# Sunrise.net
KiCad netlist of a schematic drawn in EAGLE
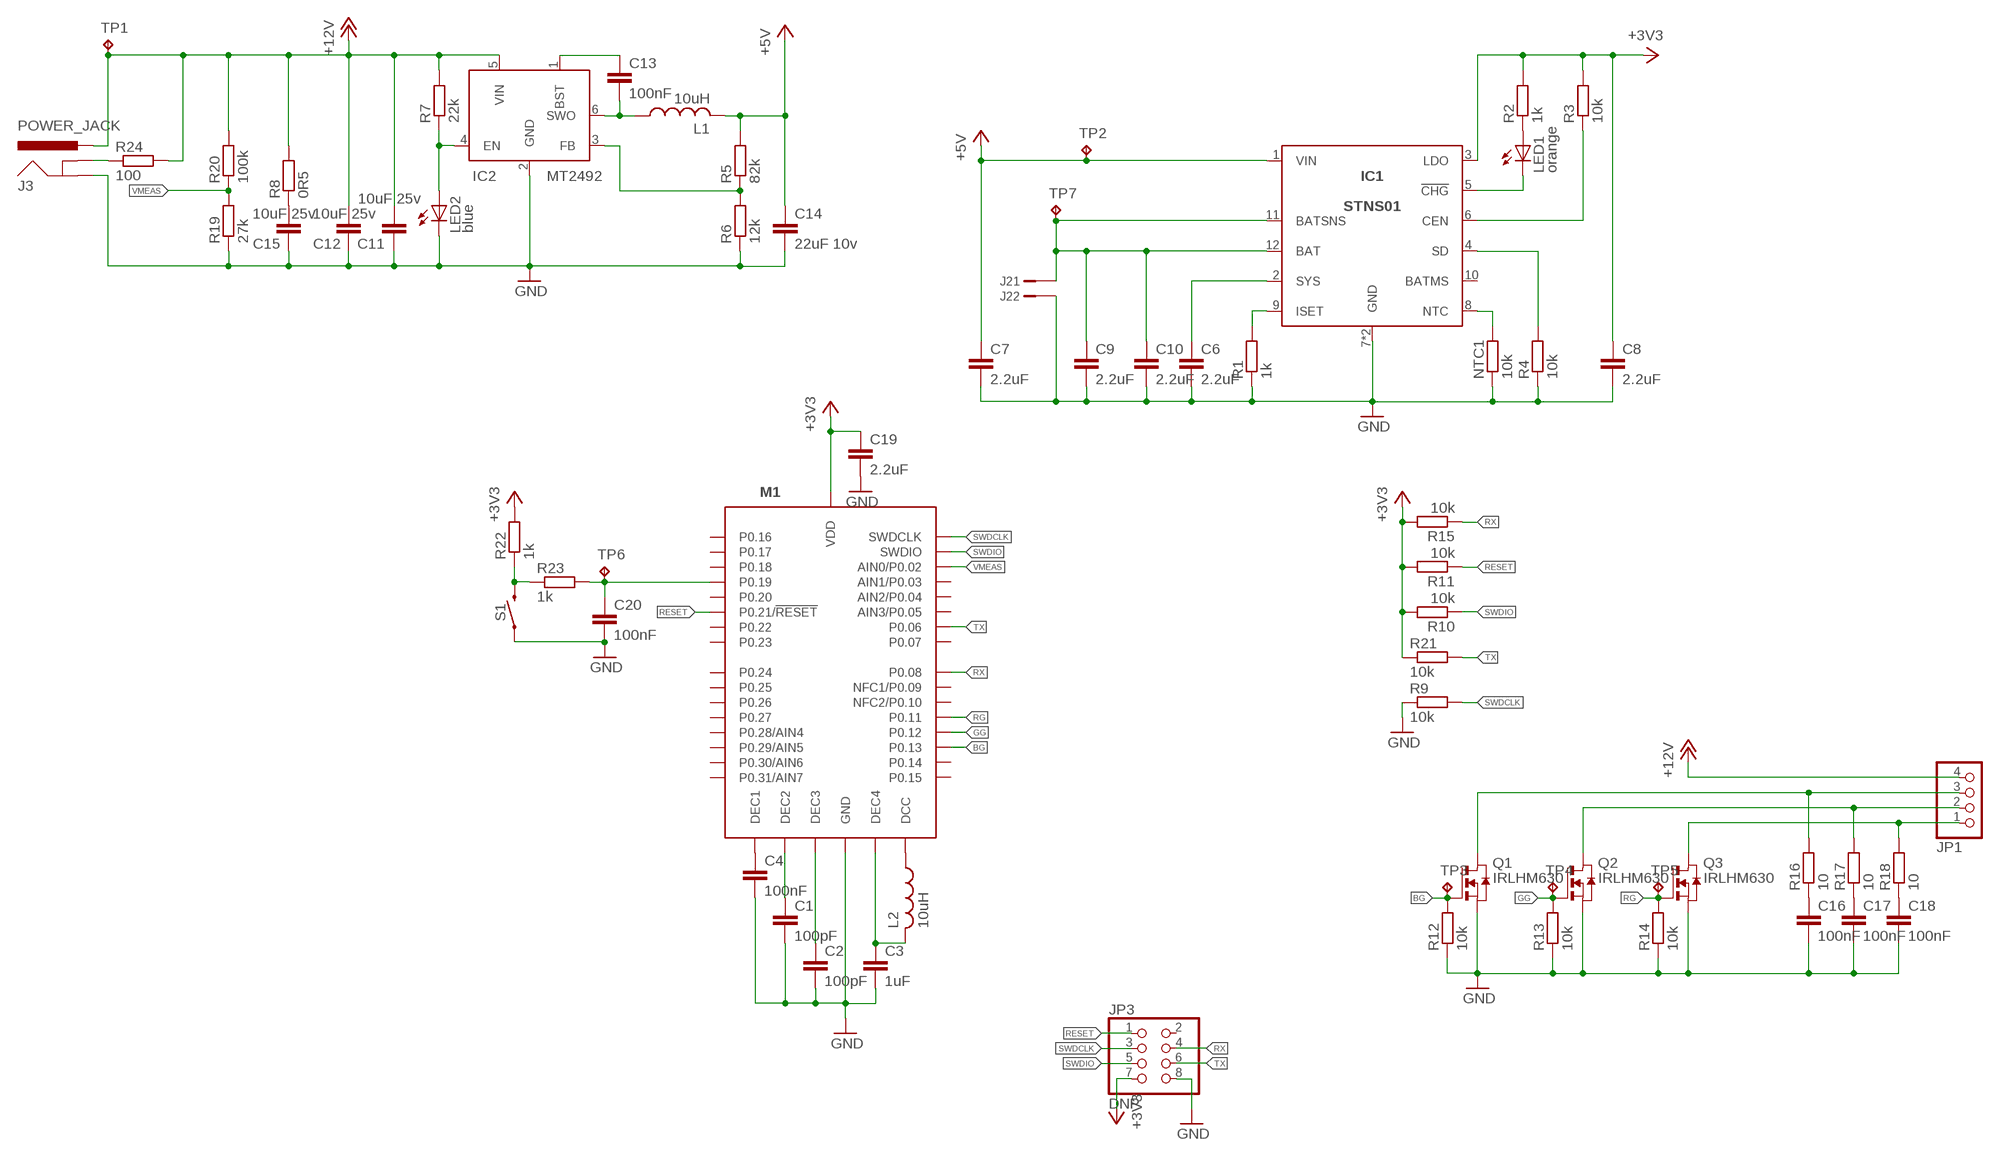
[diagram p0: schematic, sheet 1]

(export (version "E")
  (design (tool "Eeschema 10.0.6"))
  (components
    (comp (ref "C1")
      (value "100pF")
      (footprint "eagle-import:C0402K")
      (libsource (lib "eagle-import") (part "C-EUC0402K"))
    )
    (comp (ref "C2")
      (value "100pF")
      (footprint "eagle-import:C0402K")
      (libsource (lib "eagle-import") (part "C-EUC0402K"))
    )
    (comp (ref "C3")
      (value "1uF")
      (footprint "eagle-import:C0603K")
      (libsource (lib "eagle-import") (part "C-EUC0603K"))
    )
    (comp (ref "C4")
      (value "100nF")
      (footprint "eagle-import:C0402K")
      (libsource (lib "eagle-import") (part "C-EUC0402K"))
    )
    (comp (ref "C6")
      (value "2.2uF")
      (footprint "eagle-import:C0603K")
      (libsource (lib "eagle-import") (part "C-EUC0603K"))
    )
    (comp (ref "C7")
      (value "2.2uF")
      (footprint "eagle-import:C0603K")
      (libsource (lib "eagle-import") (part "C-EUC0603K"))
    )
    (comp (ref "C8")
      (value "2.2uF")
      (footprint "eagle-import:C0603K")
      (libsource (lib "eagle-import") (part "C-EUC0603K"))
    )
    (comp (ref "C9")
      (value "2.2uF")
      (footprint "eagle-import:C0603K")
      (libsource (lib "eagle-import") (part "C-EUC0603K"))
    )
    (comp (ref "C10")
      (value "2.2uF")
      (footprint "eagle-import:C0603K")
      (libsource (lib "eagle-import") (part "C-EUC0603K"))
    )
    (comp (ref "C11")
      (value "10uF 25v")
      (footprint "eagle-import:C1206K")
      (libsource (lib "eagle-import") (part "C-EUC1206K"))
    )
    (comp (ref "C12")
      (value "10uF 25v")
      (footprint "eagle-import:C1206K")
      (libsource (lib "eagle-import") (part "C-EUC1206K"))
    )
    (comp (ref "C13")
      (value "100nF")
      (footprint "eagle-import:C0402K")
      (libsource (lib "eagle-import") (part "C-EUC0402K"))
    )
    (comp (ref "C14")
      (value "22uF 10v")
      (footprint "eagle-import:C1206K")
      (libsource (lib "eagle-import") (part "C-EUC1206K"))
    )
    (comp (ref "C15")
      (value "10uF 25v")
      (footprint "eagle-import:C1206K")
      (libsource (lib "eagle-import") (part "C-EUC1206K"))
    )
    (comp (ref "C16")
      (value "100nF")
      (footprint "eagle-import:C0402K")
      (libsource (lib "eagle-import") (part "C-EUC0402K"))
    )
    (comp (ref "C17")
      (value "100nF")
      (footprint "eagle-import:C0402K")
      (libsource (lib "eagle-import") (part "C-EUC0402K"))
    )
    (comp (ref "C18")
      (value "100nF")
      (footprint "eagle-import:C0402K")
      (libsource (lib "eagle-import") (part "C-EUC0402K"))
    )
    (comp (ref "C19")
      (value "2.2uF")
      (footprint "eagle-import:C0603K")
      (libsource (lib "eagle-import") (part "C-EUC0603K"))
    )
    (comp (ref "C20")
      (value "100nF")
      (footprint "eagle-import:C0402K")
      (libsource (lib "eagle-import") (part "C-EUC0402K"))
    )
    (comp (ref "IC1")
      (value "STNS01")
      (footprint "eagle-import:DFN12L-3MM")
      (libsource (lib "eagle-import") (part "STNS01"))
    )
    (comp (ref "IC2")
      (value "MT2492")
      (footprint "eagle-import:SOT23-6")
      (libsource (lib "eagle-import") (part "MT2492"))
    )
    (comp (ref "J2")
      (value "B2B-PH-K-S")
      (footprint "eagle-import:B2B-PH-K-S")
      (libsource (lib "eagle-import") (part "B2B-PH-K-S"))
    )
    (comp (ref "J3")
      (value "POWER_JACK")
      (footprint "eagle-import:POWER_JACK_PTH")
      (libsource (lib "eagle-import") (part "POWER_JACK"))
    )
    (comp (ref "JP1")
      (value "PINHD-1X4/90")
      (footprint "eagle-import:1X04_90")
      (libsource (lib "eagle-import") (part "PINHD-1X4/90"))
    )
    (comp (ref "JP3")
      (value "DNP")
      (footprint "eagle-import:2X04")
      (libsource (lib "eagle-import") (part "PINHD-2X4"))
    )
    (comp (ref "L1")
      (value "10uH")
      (footprint "eagle-import:2020-5050")
      (libsource (lib "eagle-import") (part "INDUCTOR5050"))
    )
    (comp (ref "L2")
      (value "10uH")
      (footprint "eagle-import:0603-1608")
      (libsource (lib "eagle-import") (part "INDUCTOR1608"))
    )
    (comp (ref "LED1")
      (value "orange")
      (footprint "eagle-import:CHIP-LED0603")
      (libsource (lib "eagle-import") (part "LEDCHIP-LED0603"))
    )
    (comp (ref "LED2")
      (value "blue")
      (footprint "eagle-import:CHIP-LED0603")
      (libsource (lib "eagle-import") (part "LEDCHIP-LED0603"))
    )
    (comp (ref "M1")
      (value "E73-2G4M04S")
      (footprint "eagle-import:E73-2GM404S")
      (libsource (lib "eagle-import") (part "E73-2G4M04S"))
    )
    (comp (ref "NTC1")
      (value "10k")
      (footprint "eagle-import:R0402")
      (libsource (lib "eagle-import") (part "R-EU_R0402"))
    )
    (comp (ref "Q1")
      (value "IRLHM630")
      (footprint "eagle-import:MLP8-33")
      (libsource (lib "eagle-import") (part "NMOS-MLP8-33"))
    )
    (comp (ref "Q2")
      (value "IRLHM630")
      (footprint "eagle-import:MLP8-33")
      (libsource (lib "eagle-import") (part "NMOS-MLP8-33"))
    )
    (comp (ref "Q3")
      (value "IRLHM630")
      (footprint "eagle-import:MLP8-33")
      (libsource (lib "eagle-import") (part "NMOS-MLP8-33"))
    )
    (comp (ref "R1")
      (value "1k")
      (footprint "eagle-import:R0402")
      (libsource (lib "eagle-import") (part "R-EU_R0402"))
    )
    (comp (ref "R2")
      (value "1k")
      (footprint "eagle-import:R0402")
      (libsource (lib "eagle-import") (part "R-EU_R0402"))
    )
    (comp (ref "R3")
      (value "10k")
      (footprint "eagle-import:R0402")
      (libsource (lib "eagle-import") (part "R-EU_R0402"))
    )
    (comp (ref "R4")
      (value "10k")
      (footprint "eagle-import:R0402")
      (libsource (lib "eagle-import") (part "R-EU_R0402"))
    )
    (comp (ref "R5")
      (value "82k")
      (footprint "eagle-import:R0402")
      (libsource (lib "eagle-import") (part "R-EU_R0402"))
    )
    (comp (ref "R6")
      (value "12k")
      (footprint "eagle-import:R0402")
      (libsource (lib "eagle-import") (part "R-EU_R0402"))
    )
    (comp (ref "R7")
      (value "22k")
      (footprint "eagle-import:R0402")
      (libsource (lib "eagle-import") (part "R-EU_R0402"))
    )
    (comp (ref "R8")
      (value "0R5")
      (footprint "eagle-import:R0402")
      (libsource (lib "eagle-import") (part "R-EU_R0402"))
    )
    (comp (ref "R9")
      (value "10k")
      (footprint "eagle-import:R0402")
      (libsource (lib "eagle-import") (part "R-EU_R0402"))
    )
    (comp (ref "R10")
      (value "10k")
      (footprint "eagle-import:R0402")
      (libsource (lib "eagle-import") (part "R-EU_R0402"))
    )
    (comp (ref "R11")
      (value "10k")
      (footprint "eagle-import:R0402")
      (libsource (lib "eagle-import") (part "R-EU_R0402"))
    )
    (comp (ref "R12")
      (value "10k")
      (footprint "eagle-import:R0402")
      (libsource (lib "eagle-import") (part "R-EU_R0402"))
    )
    (comp (ref "R13")
      (value "10k")
      (footprint "eagle-import:R0402")
      (libsource (lib "eagle-import") (part "R-EU_R0402"))
    )
    (comp (ref "R14")
      (value "10k")
      (footprint "eagle-import:R0402")
      (libsource (lib "eagle-import") (part "R-EU_R0402"))
    )
    (comp (ref "R15")
      (value "10k")
      (footprint "eagle-import:R0402")
      (libsource (lib "eagle-import") (part "R-EU_R0402"))
    )
    (comp (ref "R16")
      (value "10")
      (footprint "eagle-import:R0402")
      (libsource (lib "eagle-import") (part "R-EU_R0402"))
    )
    (comp (ref "R17")
      (value "10")
      (footprint "eagle-import:R0402")
      (libsource (lib "eagle-import") (part "R-EU_R0402"))
    )
    (comp (ref "R18")
      (value "10")
      (footprint "eagle-import:R0402")
      (libsource (lib "eagle-import") (part "R-EU_R0402"))
    )
    (comp (ref "R19")
      (value "27k")
      (footprint "eagle-import:R0402")
      (libsource (lib "eagle-import") (part "R-EU_R0402"))
    )
    (comp (ref "R20")
      (value "100k")
      (footprint "eagle-import:R0402")
      (libsource (lib "eagle-import") (part "R-EU_R0402"))
    )
    (comp (ref "R21")
      (value "10k")
      (footprint "eagle-import:R0402")
      (libsource (lib "eagle-import") (part "R-EU_R0402"))
    )
    (comp (ref "R22")
      (value "1k")
      (footprint "eagle-import:R0402")
      (libsource (lib "eagle-import") (part "R-EU_R0402"))
    )
    (comp (ref "R23")
      (value "1k")
      (footprint "eagle-import:R0402")
      (libsource (lib "eagle-import") (part "R-EU_R0402"))
    )
    (comp (ref "R24")
      (value "100")
      (footprint "eagle-import:R0402")
      (libsource (lib "eagle-import") (part "R-EU_R0402"))
    )
    (comp (ref "S1")
      (value "MOMENTARY-SWITCH-SPST-SMD-5.2MM")
      (footprint "eagle-import:TACTILE_SWITCH_SMD_5.2MM")
      (libsource (lib "eagle-import") (part "MOMENTARY-SWITCH-SPST-SMD-5.2MM"))
    )
    (comp (ref "TP1")
      (value "TPTP10R")
      (footprint "eagle-import:TP10R")
      (libsource (lib "eagle-import") (part "TPTP10R"))
    )
    (comp (ref "TP2")
      (value "TPTP10R")
      (footprint "eagle-import:TP10R")
      (libsource (lib "eagle-import") (part "TPTP10R"))
    )
    (comp (ref "TP3")
      (value "TPTP10R")
      (footprint "eagle-import:TP10R")
      (libsource (lib "eagle-import") (part "TPTP10R"))
    )
    (comp (ref "TP4")
      (value "TPTP10R")
      (footprint "eagle-import:TP10R")
      (libsource (lib "eagle-import") (part "TPTP10R"))
    )
    (comp (ref "TP5")
      (value "TPTP10R")
      (footprint "eagle-import:TP10R")
      (libsource (lib "eagle-import") (part "TPTP10R"))
    )
    (comp (ref "TP6")
      (value "TPTP10R")
      (footprint "eagle-import:TP10R")
      (libsource (lib "eagle-import") (part "TPTP10R"))
    )
    (comp (ref "TP7")
      (value "TPTP10R")
      (footprint "eagle-import:TP10R")
      (libsource (lib "eagle-import") (part "TPTP10R"))
    )
  )
  (nets
    (net (code "1") (name "+3V3") (class "Default")
      (node (ref "C19") (pin "1") (pinfunction "1_1") (pintype "passive"))
      (node (ref "C8") (pin "1") (pinfunction "1_1") (pintype "passive"))
      (node (ref "IC1") (pin "3") (pinfunction "LDO_3") (pintype "power_in"))
      (node (ref "JP3") (pin "7") (pinfunction "7_7") (pintype "passive"))
      (node (ref "M1") (pin "16") (pinfunction "VDD_16") (pintype "power_in"))
      (node (ref "R10") (pin "2") (pinfunction "2_2") (pintype "passive"))
      (node (ref "R11") (pin "2") (pinfunction "2_2") (pintype "passive"))
      (node (ref "R15") (pin "2") (pinfunction "2_2") (pintype "passive"))
      (node (ref "R2") (pin "2") (pinfunction "2_2") (pintype "passive"))
      (node (ref "R21") (pin "1") (pinfunction "1_1") (pintype "passive"))
      (node (ref "R22") (pin "2") (pinfunction "2_2") (pintype "passive"))
      (node (ref "R3") (pin "2") (pinfunction "2_2") (pintype "passive"))
    )
    (net (code "2") (name "+5V") (class "Default")
      (node (ref "C14") (pin "1") (pinfunction "1_1") (pintype "passive"))
      (node (ref "C7") (pin "1") (pinfunction "1_1") (pintype "passive"))
      (node (ref "IC1") (pin "1") (pinfunction "VIN_1") (pintype "power_in"))
      (node (ref "L1") (pin "2") (pinfunction "2_2") (pintype "passive"))
      (node (ref "R5") (pin "2") (pinfunction "2_2") (pintype "passive"))
      (node (ref "TP2") (pin "TP") (pinfunction "TP_TP") (pintype "input"))
    )
    (net (code "3") (name "+12V") (class "Default")
      (node (ref "C11") (pin "1") (pinfunction "1_1") (pintype "passive"))
      (node (ref "C12") (pin "1") (pinfunction "1_1") (pintype "passive"))
      (node (ref "IC2") (pin "5") (pinfunction "VIN_5") (pintype "power_in"))
      (node (ref "J3") (pin "PWR") (pinfunction "PWR_PWR") (pintype "bidirectional"))
      (node (ref "JP1") (pin "4") (pinfunction "4_4") (pintype "passive"))
      (node (ref "R20") (pin "2") (pinfunction "2_2") (pintype "passive"))
      (node (ref "R24") (pin "2") (pinfunction "2_2") (pintype "passive"))
      (node (ref "R7") (pin "2") (pinfunction "2_2") (pintype "passive"))
      (node (ref "R8") (pin "2") (pinfunction "2_2") (pintype "passive"))
      (node (ref "TP1") (pin "TP") (pinfunction "TP_TP") (pintype "input"))
    )
    (net (code "4") (name "BG") (class "Default")
      (node (ref "M1") (pin "28") (pinfunction "P0.13_28") (pintype "bidirectional"))
      (node (ref "Q1") (pin "GATE") (pinfunction "G_GATE") (pintype "passive"))
      (node (ref "R12") (pin "2") (pinfunction "2_2") (pintype "passive"))
      (node (ref "TP3") (pin "TP") (pinfunction "TP_TP") (pintype "input"))
    )
    (net (code "5") (name "GG") (class "Default")
      (node (ref "M1") (pin "27") (pinfunction "P0.12_27") (pintype "bidirectional"))
      (node (ref "Q2") (pin "GATE") (pinfunction "G_GATE") (pintype "passive"))
      (node (ref "R13") (pin "2") (pinfunction "2_2") (pintype "passive"))
      (node (ref "TP4") (pin "TP") (pinfunction "TP_TP") (pintype "input"))
    )
    (net (code "6") (name "GND") (class "Default")
      (node (ref "C1") (pin "2") (pinfunction "2_2") (pintype "passive"))
      (node (ref "C10") (pin "2") (pinfunction "2_2") (pintype "passive"))
      (node (ref "C11") (pin "2") (pinfunction "2_2") (pintype "passive"))
      (node (ref "C12") (pin "2") (pinfunction "2_2") (pintype "passive"))
      (node (ref "C14") (pin "2") (pinfunction "2_2") (pintype "passive"))
      (node (ref "C15") (pin "2") (pinfunction "2_2") (pintype "passive"))
      (node (ref "C16") (pin "2") (pinfunction "2_2") (pintype "passive"))
      (node (ref "C17") (pin "2") (pinfunction "2_2") (pintype "passive"))
      (node (ref "C18") (pin "2") (pinfunction "2_2") (pintype "passive"))
      (node (ref "C19") (pin "2") (pinfunction "2_2") (pintype "passive"))
      (node (ref "C2") (pin "2") (pinfunction "2_2") (pintype "passive"))
      (node (ref "C20") (pin "2") (pinfunction "2_2") (pintype "passive"))
      (node (ref "C3") (pin "2") (pinfunction "2_2") (pintype "passive"))
      (node (ref "C4") (pin "2") (pinfunction "2_2") (pintype "passive"))
      (node (ref "C6") (pin "2") (pinfunction "2_2") (pintype "passive"))
      (node (ref "C7") (pin "2") (pinfunction "2_2") (pintype "passive"))
      (node (ref "C8") (pin "2") (pinfunction "2_2") (pintype "passive"))
      (node (ref "C9") (pin "2") (pinfunction "2_2") (pintype "passive"))
      (node (ref "IC1") (pin "7") (pinfunction "GND_7") (pintype "power_in"))
      (node (ref "IC1") (pin "PAD") (pinfunction "GND_PAD") (pintype "power_in"))
      (node (ref "IC2") (pin "2") (pinfunction "GND_2") (pintype "power_in"))
      (node (ref "J2") (pin "2") (pinfunction "1_2") (pintype "passive"))
      (node (ref "J3") (pin "GND") (pinfunction "GND_GND") (pintype "bidirectional"))
      (node (ref "JP3") (pin "8") (pinfunction "8_8") (pintype "passive"))
      (node (ref "LED2") (pin "C") (pinfunction "C_C") (pintype "passive"))
      (node (ref "M1") (pin "0") (pinfunction "GND_0") (pintype "power_in"))
      (node (ref "M1") (pin "1") (pinfunction "GND_1") (pintype "power_in"))
      (node (ref "M1") (pin "15") (pinfunction "GND_15") (pintype "power_in"))
      (node (ref "M1") (pin "2") (pinfunction "GND_2") (pintype "power_in"))
      (node (ref "M1") (pin "42") (pinfunction "GND_42") (pintype "power_in"))
      (node (ref "M1") (pin "43") (pinfunction "GND_43") (pintype "power_in"))
      (node (ref "NTC1") (pin "1") (pinfunction "1_1") (pintype "passive"))
      (node (ref "Q1") (pin "S1") (pinfunction "S_S1") (pintype "passive"))
      (node (ref "Q1") (pin "S2") (pinfunction "S_S2") (pintype "passive"))
      (node (ref "Q1") (pin "S3") (pinfunction "S_S3") (pintype "passive"))
      (node (ref "Q2") (pin "S1") (pinfunction "S_S1") (pintype "passive"))
      (node (ref "Q2") (pin "S2") (pinfunction "S_S2") (pintype "passive"))
      (node (ref "Q2") (pin "S3") (pinfunction "S_S3") (pintype "passive"))
      (node (ref "Q3") (pin "S1") (pinfunction "S_S1") (pintype "passive"))
      (node (ref "Q3") (pin "S2") (pinfunction "S_S2") (pintype "passive"))
      (node (ref "Q3") (pin "S3") (pinfunction "S_S3") (pintype "passive"))
      (node (ref "R1") (pin "1") (pinfunction "1_1") (pintype "passive"))
      (node (ref "R12") (pin "1") (pinfunction "1_1") (pintype "passive"))
      (node (ref "R13") (pin "1") (pinfunction "1_1") (pintype "passive"))
      (node (ref "R14") (pin "1") (pinfunction "1_1") (pintype "passive"))
      (node (ref "R19") (pin "1") (pinfunction "1_1") (pintype "passive"))
      (node (ref "R4") (pin "1") (pinfunction "1_1") (pintype "passive"))
      (node (ref "R6") (pin "1") (pinfunction "1_1") (pintype "passive"))
      (node (ref "R9") (pin "1") (pinfunction "1_1") (pintype "passive"))
      (node (ref "S1") (pin "1") (pinfunction "1_1") (pintype "passive"))
    )
    (net (code "7") (name "Net-(C15-Pad1)") (class "Default")
      (node (ref "C15") (pin "1") (pinfunction "1_1") (pintype "passive"))
      (node (ref "R8") (pin "1") (pinfunction "1_1") (pintype "passive"))
    )
    (net (code "8") (name "Net-(C16-Pad1)") (class "Default")
      (node (ref "C16") (pin "1") (pinfunction "1_1") (pintype "passive"))
      (node (ref "R16") (pin "1") (pinfunction "1_1") (pintype "passive"))
    )
    (net (code "9") (name "Net-(C17-Pad1)") (class "Default")
      (node (ref "C17") (pin "1") (pinfunction "1_1") (pintype "passive"))
      (node (ref "R17") (pin "1") (pinfunction "1_1") (pintype "passive"))
    )
    (net (code "10") (name "Net-(C18-Pad1)") (class "Default")
      (node (ref "C18") (pin "1") (pinfunction "1_1") (pintype "passive"))
      (node (ref "R18") (pin "1") (pinfunction "1_1") (pintype "passive"))
    )
    (net (code "11") (name "Net-(IC1-BAT)") (class "Default")
      (node (ref "C10") (pin "1") (pinfunction "1_1") (pintype "passive"))
      (node (ref "C9") (pin "1") (pinfunction "1_1") (pintype "passive"))
      (node (ref "IC1") (pin "11") (pinfunction "BATSNS_11") (pintype "bidirectional"))
      (node (ref "IC1") (pin "12") (pinfunction "BAT_12") (pintype "bidirectional"))
      (node (ref "J2") (pin "1") (pinfunction "1_1") (pintype "passive"))
      (node (ref "TP7") (pin "TP") (pinfunction "TP_TP") (pintype "input"))
    )
    (net (code "12") (name "Net-(IC1-CEN)") (class "Default")
      (node (ref "IC1") (pin "6") (pinfunction "CEN_6") (pintype "bidirectional"))
      (node (ref "R3") (pin "1") (pinfunction "1_1") (pintype "passive"))
    )
    (net (code "13") (name "Net-(IC1-ISET)") (class "Default")
      (node (ref "IC1") (pin "9") (pinfunction "ISET_9") (pintype "bidirectional"))
      (node (ref "R1") (pin "2") (pinfunction "2_2") (pintype "passive"))
    )
    (net (code "14") (name "Net-(IC1-NTC)") (class "Default")
      (node (ref "IC1") (pin "8") (pinfunction "NTC_8") (pintype "bidirectional"))
      (node (ref "NTC1") (pin "2") (pinfunction "2_2") (pintype "passive"))
    )
    (net (code "15") (name "Net-(IC1-SD)") (class "Default")
      (node (ref "IC1") (pin "4") (pinfunction "SD_4") (pintype "bidirectional"))
      (node (ref "R4") (pin "2") (pinfunction "2_2") (pintype "passive"))
    )
    (net (code "16") (name "Net-(IC1-SYS)") (class "Default")
      (node (ref "C6") (pin "1") (pinfunction "1_1") (pintype "passive"))
      (node (ref "IC1") (pin "2") (pinfunction "SYS_2") (pintype "bidirectional"))
    )
    (net (code "17") (name "Net-(IC1-~{CHG})") (class "Default")
      (node (ref "IC1") (pin "5") (pinfunction "~{CHG}_5") (pintype "bidirectional"))
      (node (ref "LED1") (pin "C") (pinfunction "C_C") (pintype "passive"))
    )
    (net (code "18") (name "Net-(IC2-BST)") (class "Default")
      (node (ref "C13") (pin "1") (pinfunction "1_1") (pintype "passive"))
      (node (ref "IC2") (pin "1") (pinfunction "BST_1") (pintype "input"))
    )
    (net (code "19") (name "Net-(IC2-EN)") (class "Default")
      (node (ref "IC2") (pin "4") (pinfunction "EN_4") (pintype "input"))
      (node (ref "LED2") (pin "A") (pinfunction "A_A") (pintype "passive"))
      (node (ref "R7") (pin "1") (pinfunction "1_1") (pintype "passive"))
    )
    (net (code "20") (name "Net-(IC2-FB)") (class "Default")
      (node (ref "IC2") (pin "3") (pinfunction "FB_3") (pintype "input"))
      (node (ref "R5") (pin "1") (pinfunction "1_1") (pintype "passive"))
      (node (ref "R6") (pin "2") (pinfunction "2_2") (pintype "passive"))
    )
    (net (code "21") (name "Net-(IC2-SWO)") (class "Default")
      (node (ref "C13") (pin "2") (pinfunction "2_2") (pintype "passive"))
      (node (ref "IC2") (pin "6") (pinfunction "SWO_6") (pintype "output"))
      (node (ref "L1") (pin "1") (pinfunction "1_1") (pintype "passive"))
    )
    (net (code "22") (name "Net-(J3-PadGNDBREAK)") (class "Default")
      (node (ref "J3") (pin "GNDBREAK") (pinfunction "GNDBREAK_GNDBREAK") (pintype "bidirectional"))
      (node (ref "R24") (pin "1") (pinfunction "1_1") (pintype "passive"))
    )
    (net (code "23") (name "Net-(JP1-Pad1)") (class "Default")
      (node (ref "JP1") (pin "1") (pinfunction "1_1") (pintype "passive"))
      (node (ref "Q3") (pin "D1") (pinfunction "D_D1") (pintype "passive"))
      (node (ref "Q3") (pin "D2") (pinfunction "D_D2") (pintype "passive"))
      (node (ref "Q3") (pin "D3") (pinfunction "D_D3") (pintype "passive"))
      (node (ref "Q3") (pin "D4") (pinfunction "D_D4") (pintype "passive"))
      (node (ref "Q3") (pin "DRAIN0") (pinfunction "D_DRAIN0") (pintype "passive"))
      (node (ref "R18") (pin "2") (pinfunction "2_2") (pintype "passive"))
    )
    (net (code "24") (name "Net-(JP1-Pad2)") (class "Default")
      (node (ref "JP1") (pin "2") (pinfunction "2_2") (pintype "passive"))
      (node (ref "Q2") (pin "D1") (pinfunction "D_D1") (pintype "passive"))
      (node (ref "Q2") (pin "D2") (pinfunction "D_D2") (pintype "passive"))
      (node (ref "Q2") (pin "D3") (pinfunction "D_D3") (pintype "passive"))
      (node (ref "Q2") (pin "D4") (pinfunction "D_D4") (pintype "passive"))
      (node (ref "Q2") (pin "DRAIN0") (pinfunction "D_DRAIN0") (pintype "passive"))
      (node (ref "R17") (pin "2") (pinfunction "2_2") (pintype "passive"))
    )
    (net (code "25") (name "Net-(JP1-Pad3)") (class "Default")
      (node (ref "JP1") (pin "3") (pinfunction "3_3") (pintype "passive"))
      (node (ref "Q1") (pin "D1") (pinfunction "D_D1") (pintype "passive"))
      (node (ref "Q1") (pin "D2") (pinfunction "D_D2") (pintype "passive"))
      (node (ref "Q1") (pin "D3") (pinfunction "D_D3") (pintype "passive"))
      (node (ref "Q1") (pin "D4") (pinfunction "D_D4") (pintype "passive"))
      (node (ref "Q1") (pin "DRAIN0") (pinfunction "D_DRAIN0") (pintype "passive"))
      (node (ref "R16") (pin "2") (pinfunction "2_2") (pintype "passive"))
    )
    (net (code "26") (name "Net-(LED1-PadA)") (class "Default")
      (node (ref "LED1") (pin "A") (pinfunction "A_A") (pintype "passive"))
      (node (ref "R2") (pin "1") (pinfunction "1_1") (pintype "passive"))
    )
    (net (code "27") (name "Net-(M1-DCC)") (class "Default")
      (node (ref "L2") (pin "1") (pinfunction "1_1") (pintype "passive"))
      (node (ref "M1") (pin "13") (pinfunction "DCC_13") (pintype "bidirectional"))
    )
    (net (code "28") (name "Net-(M1-DEC1)") (class "Default")
      (node (ref "C4") (pin "1") (pinfunction "1_1") (pintype "passive"))
      (node (ref "M1") (pin "14") (pinfunction "DEC1_14") (pintype "bidirectional"))
    )
    (net (code "29") (name "Net-(M1-DEC2)") (class "Default")
      (node (ref "C1") (pin "1") (pinfunction "1_1") (pintype "passive"))
      (node (ref "M1") (pin "3") (pinfunction "DEC2_3") (pintype "bidirectional"))
    )
    (net (code "30") (name "Net-(M1-DEC3)") (class "Default")
      (node (ref "C2") (pin "1") (pinfunction "1_1") (pintype "passive"))
      (node (ref "M1") (pin "4") (pinfunction "DEC3_4") (pintype "bidirectional"))
    )
    (net (code "31") (name "Net-(M1-DEC4)") (class "Default")
      (node (ref "C3") (pin "1") (pinfunction "1_1") (pintype "passive"))
      (node (ref "L2") (pin "2") (pinfunction "2_2") (pintype "passive"))
      (node (ref "M1") (pin "12") (pinfunction "DEC4_12") (pintype "bidirectional"))
    )
    (net (code "32") (name "Net-(M1-P0.19)") (class "Default")
      (node (ref "C20") (pin "1") (pinfunction "1_1") (pintype "passive"))
      (node (ref "M1") (pin "34") (pinfunction "P0.19_34") (pintype "bidirectional"))
      (node (ref "R23") (pin "2") (pinfunction "2_2") (pintype "passive"))
      (node (ref "TP6") (pin "TP") (pinfunction "TP_TP") (pintype "input"))
    )
    (net (code "33") (name "Net-(S1-2)") (class "Default")
      (node (ref "R22") (pin "1") (pinfunction "1_1") (pintype "passive"))
      (node (ref "R23") (pin "1") (pinfunction "1_1") (pintype "passive"))
      (node (ref "S1") (pin "3") (pinfunction "2_3") (pintype "passive"))
    )
    (net (code "34") (name "RESET") (class "Default")
      (node (ref "JP3") (pin "1") (pinfunction "1_1") (pintype "passive"))
      (node (ref "M1") (pin "36") (pinfunction "P0.21/~{RESET}_36") (pintype "bidirectional"))
      (node (ref "R11") (pin "1") (pinfunction "1_1") (pintype "passive"))
    )
    (net (code "35") (name "RG") (class "Default")
      (node (ref "M1") (pin "26") (pinfunction "P0.11_26") (pintype "bidirectional"))
      (node (ref "Q3") (pin "GATE") (pinfunction "G_GATE") (pintype "passive"))
      (node (ref "R14") (pin "2") (pinfunction "2_2") (pintype "passive"))
      (node (ref "TP5") (pin "TP") (pinfunction "TP_TP") (pintype "input"))
    )
    (net (code "36") (name "RX") (class "Default")
      (node (ref "JP3") (pin "4") (pinfunction "4_4") (pintype "passive"))
      (node (ref "M1") (pin "23") (pinfunction "P0.08_23") (pintype "bidirectional"))
      (node (ref "R15") (pin "1") (pinfunction "1_1") (pintype "passive"))
    )
    (net (code "37") (name "SWDCLK") (class "Default")
      (node (ref "JP3") (pin "3") (pinfunction "3_3") (pintype "passive"))
      (node (ref "M1") (pin "37") (pinfunction "SWDCLK_37") (pintype "input"))
      (node (ref "R9") (pin "2") (pinfunction "2_2") (pintype "passive"))
    )
    (net (code "38") (name "SWDIO") (class "Default")
      (node (ref "JP3") (pin "5") (pinfunction "5_5") (pintype "passive"))
      (node (ref "M1") (pin "38") (pinfunction "SWDIO_38") (pintype "bidirectional"))
      (node (ref "R10") (pin "1") (pinfunction "1_1") (pintype "passive"))
    )
    (net (code "39") (name "TX") (class "Default")
      (node (ref "JP3") (pin "6") (pinfunction "6_6") (pintype "passive"))
      (node (ref "M1") (pin "21") (pinfunction "P0.06_21") (pintype "bidirectional"))
      (node (ref "R21") (pin "2") (pinfunction "2_2") (pintype "passive"))
    )
    (net (code "40") (name "VMEAS") (class "Default")
      (node (ref "M1") (pin "17") (pinfunction "AIN0/P0.02_17") (pintype "bidirectional"))
      (node (ref "R19") (pin "2") (pinfunction "2_2") (pintype "passive"))
      (node (ref "R20") (pin "1") (pinfunction "1_1") (pintype "passive"))
    )
    (net (code "41") (name "unconnected-(IC1-BATMS-Pad10)") (class "Default")
      (node (ref "IC1") (pin "10") (pinfunction "BATMS_10") (pintype "bidirectional"))
    )
    (net (code "42") (name "unconnected-(JP3-Pad2)") (class "Default")
      (node (ref "JP3") (pin "2") (pinfunction "2_2") (pintype "passive"))
    )
    (net (code "43") (name "unconnected-(M1-AIN1{slash}P0.03-Pad18)") (class "Default")
      (node (ref "M1") (pin "18") (pinfunction "AIN1/P0.03_18") (pintype "bidirectional"))
    )
    (net (code "44") (name "unconnected-(M1-AIN2{slash}P0.04-Pad19)") (class "Default")
      (node (ref "M1") (pin "19") (pinfunction "AIN2/P0.04_19") (pintype "bidirectional"))
    )
    (net (code "45") (name "unconnected-(M1-AIN3{slash}P0.05-Pad20)") (class "Default")
      (node (ref "M1") (pin "20") (pinfunction "AIN3/P0.05_20") (pintype "bidirectional"))
    )
    (net (code "46") (name "unconnected-(M1-NFC1{slash}P0.09-Pad24)") (class "Default")
      (node (ref "M1") (pin "24") (pinfunction "NFC1/P0.09_24") (pintype "bidirectional"))
    )
    (net (code "47") (name "unconnected-(M1-NFC2{slash}P0.10-Pad25)") (class "Default")
      (node (ref "M1") (pin "25") (pinfunction "NFC2/P0.10_25") (pintype "bidirectional"))
    )
    (net (code "48") (name "unconnected-(M1-P0.07-Pad22)") (class "Default")
      (node (ref "M1") (pin "22") (pinfunction "P0.07_22") (pintype "bidirectional"))
    )
    (net (code "49") (name "unconnected-(M1-P0.14-Pad29)") (class "Default")
      (node (ref "M1") (pin "29") (pinfunction "P0.14_29") (pintype "bidirectional"))
    )
    (net (code "50") (name "unconnected-(M1-P0.15-Pad30)") (class "Default")
      (node (ref "M1") (pin "30") (pinfunction "P0.15_30") (pintype "bidirectional"))
    )
    (net (code "51") (name "unconnected-(M1-P0.16-Pad31)") (class "Default")
      (node (ref "M1") (pin "31") (pinfunction "P0.16_31") (pintype "bidirectional"))
    )
    (net (code "52") (name "unconnected-(M1-P0.17-Pad32)") (class "Default")
      (node (ref "M1") (pin "32") (pinfunction "P0.17_32") (pintype "bidirectional"))
    )
    (net (code "53") (name "unconnected-(M1-P0.18-Pad33)") (class "Default")
      (node (ref "M1") (pin "33") (pinfunction "P0.18_33") (pintype "bidirectional"))
    )
    (net (code "54") (name "unconnected-(M1-P0.20-Pad35)") (class "Default")
      (node (ref "M1") (pin "35") (pinfunction "P0.20_35") (pintype "bidirectional"))
    )
    (net (code "55") (name "unconnected-(M1-P0.22-Pad39)") (class "Default")
      (node (ref "M1") (pin "39") (pinfunction "P0.22_39") (pintype "bidirectional"))
    )
    (net (code "56") (name "unconnected-(M1-P0.23-Pad40)") (class "Default")
      (node (ref "M1") (pin "40") (pinfunction "P0.23_40") (pintype "bidirectional"))
    )
    (net (code "57") (name "unconnected-(M1-P0.24-Pad41)") (class "Default")
      (node (ref "M1") (pin "41") (pinfunction "P0.24_41") (pintype "bidirectional"))
    )
    (net (code "58") (name "unconnected-(M1-P0.25-Pad5)") (class "Default")
      (node (ref "M1") (pin "5") (pinfunction "P0.25_5") (pintype "bidirectional"))
    )
    (net (code "59") (name "unconnected-(M1-P0.26-Pad6)") (class "Default")
      (node (ref "M1") (pin "6") (pinfunction "P0.26_6") (pintype "bidirectional"))
    )
    (net (code "60") (name "unconnected-(M1-P0.27-Pad7)") (class "Default")
      (node (ref "M1") (pin "7") (pinfunction "P0.27_7") (pintype "bidirectional"))
    )
    (net (code "61") (name "unconnected-(M1-P0.28{slash}AIN4-Pad8)") (class "Default")
      (node (ref "M1") (pin "8") (pinfunction "P0.28/AIN4_8") (pintype "bidirectional"))
    )
    (net (code "62") (name "unconnected-(M1-P0.29{slash}AIN5-Pad9)") (class "Default")
      (node (ref "M1") (pin "9") (pinfunction "P0.29/AIN5_9") (pintype "bidirectional"))
    )
    (net (code "63") (name "unconnected-(M1-P0.30{slash}AIN6-Pad10)") (class "Default")
      (node (ref "M1") (pin "10") (pinfunction "P0.30/AIN6_10") (pintype "bidirectional"))
    )
    (net (code "64") (name "unconnected-(M1-P0.31{slash}AIN7-Pad11)") (class "Default")
      (node (ref "M1") (pin "11") (pinfunction "P0.31/AIN7_11") (pintype "bidirectional"))
    )
  )
)
